# WeatherStation.net
KiCad netlist of a schematic drawn in Altium Designer
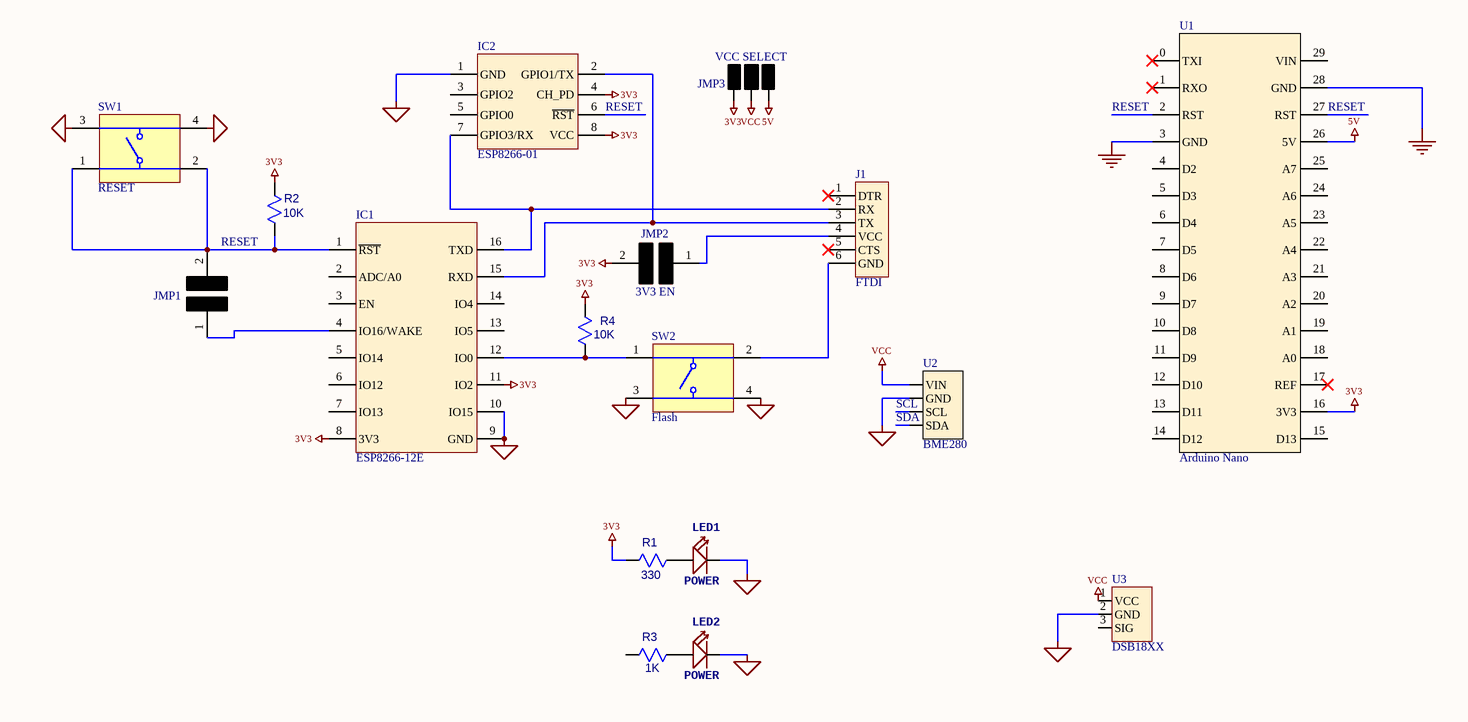
[diagram p0: WeatherStation.SchDoc]

(export (version "E")
  (design (tool "Eeschema 10.0.6"))
  (components
    (comp (ref "IC1")
      (value "ESP8266-12E")
      (footprint "ESP8266-12E")
      (fields (field (name "PART") "ESP8266-12E"))
      (libsource (lib "WeatherStation") (part "ESP8266"))
    )
    (comp (ref "IC2")
      (value "ESP8266-01")
      (footprint "ESP8266-01")
      (libsource (lib "WeatherStation") (part "ESP8266-01"))
    )
    (comp (ref "J1")
      (value "FTDI")
      (footprint "HEAD_1x6")
      (libsource (lib "WeatherStation") (part "FTDI_Connector"))
    )
    (comp (ref "JMP1") (value "JUMP") (footprint "JUMP") (libsource (lib "WeatherStation") (part "JUMP")))
    (comp (ref "JMP2") (value "3V3 EN") (footprint "JUMP") (libsource (lib "WeatherStation") (part "JUMP")))
    (comp (ref "JMP3")
      (value "VCC SELECT")
      (footprint "JMP3")
      (libsource (lib "WeatherStation") (part "JUMP_3"))
    )
    (comp (ref "LED1")
      (value "POWER")
      (footprint "LED-0805")
      (fields (field (name "MPN") "17-215UYC/S530-A3/TR8"))
      (libsource (lib "105848_revD3") (part "SMD-LED-CLEAR-YELLOW(0805)"))
    )
    (comp (ref "LED2")
      (value "POWER")
      (footprint "LED-0805")
      (fields (field (name "MPN") "17-215UYC/S530-A3/TR8"))
      (libsource (lib "105848_revD3") (part "SMD-LED-CLEAR-YELLOW(0805)"))
    )
    (comp (ref "R1")
      (value "330")
      (footprint "CAPC0805(2012)75_N")
      (description "RES_0805")
      (libsource (lib "AltiumIntegratedLibrary") (part "RES_0805"))
    )
    (comp (ref "R2")
      (value "10K")
      (footprint "CAPC0805(2012)75_N")
      (description "RES_0805")
      (libsource (lib "AltiumIntegratedLibrary") (part "RES_0805"))
    )
    (comp (ref "R3")
      (value "1K")
      (footprint "CAPC0805(2012)75_N")
      (description "RES_0805")
      (libsource (lib "AltiumIntegratedLibrary") (part "RES_0805"))
    )
    (comp (ref "R4")
      (value "10K")
      (footprint "CAPC0805(2012)75_N")
      (description "RES_0805")
      (libsource (lib "AltiumIntegratedLibrary") (part "RES_0805"))
    )
    (comp (ref "SW1")
      (value "RESET")
      (footprint "Tactile Switch")
      (libsource (lib "WeatherStation") (part "Tact Switch"))
    )
    (comp (ref "SW2")
      (value "Flash")
      (footprint "Tactile Switch")
      (libsource (lib "") (part "Tact Switch_1"))
    )
    (comp (ref "U1")
      (value "Arduino Nano")
      (footprint "Arduino Nano")
      (libsource (lib "WeatherStation") (part "Arduino Nano"))
    )
    (comp (ref "U2") (value "BME280") (footprint "BME280") (libsource (lib "WeatherStation") (part "BME280")))
    (comp (ref "U3")
      (value "DSB18XX")
      (footprint "HEAD_1x3")
      (libsource (lib "WeatherStation") (part "DALLAS_TEMP"))
    )
  )
  (nets
    (net (code "1") (name "/RESET") (class "Default")
      (node (ref "IC1") (pin "1") (pinfunction "~{RST}_1") (pintype "power_in"))
      (node (ref "IC2") (pin "6") (pinfunction "~{RST}_6") (pintype "power_in"))
      (node (ref "JMP1") (pin "2") (pintype "power_in"))
      (node (ref "R2") (pin "2") (pintype "passive"))
      (node (ref "SW1") (pin "1") (pinfunction "1_1") (pintype "passive"))
      (node (ref "SW1") (pin "2") (pinfunction "2_2") (pintype "passive"))
      (node (ref "U1") (pin "2") (pinfunction "RST_2") (pintype "power_in"))
      (node (ref "U1") (pin "27") (pinfunction "RST_27") (pintype "power_in"))
    )
    (net (code "2") (name "/SCL") (class "Default")
      (node (ref "U2") (pin "3") (pinfunction "SCL_3") (pintype "power_in"))
    )
    (net (code "3") (name "/SDA") (class "Default")
      (node (ref "U2") (pin "4") (pinfunction "SDA_4") (pintype "power_in"))
    )
    (net (code "4") (name "3V3") (class "Default")
      (node (ref "IC1") (pin "11") (pinfunction "IO2_11") (pintype "power_in"))
      (node (ref "IC1") (pin "8") (pinfunction "3V3_8") (pintype "power_in"))
      (node (ref "IC2") (pin "4") (pinfunction "CH_PD_4") (pintype "power_in"))
      (node (ref "IC2") (pin "8") (pinfunction "VCC_8") (pintype "power_in"))
      (node (ref "JMP2") (pin "2") (pintype "power_in"))
      (node (ref "JMP3") (pin "3") (pintype "power_in"))
      (node (ref "R1") (pin "2") (pintype "passive"))
      (node (ref "R2") (pin "1") (pintype "passive"))
      (node (ref "R4") (pin "1") (pintype "passive"))
      (node (ref "U1") (pin "16") (pinfunction "3V3_16") (pintype "power_in"))
    )
    (net (code "5") (name "5V") (class "Default")
      (node (ref "JMP3") (pin "2") (pintype "power_in"))
      (node (ref "U1") (pin "26") (pinfunction "5V_26") (pintype "power_in"))
    )
    (net (code "6") (name "GND") (class "Default")
      (node (ref "IC1") (pin "10") (pinfunction "IO15_10") (pintype "power_in"))
      (node (ref "IC1") (pin "9") (pinfunction "GND_9") (pintype "power_in"))
      (node (ref "IC2") (pin "1") (pinfunction "GND_1") (pintype "power_in"))
      (node (ref "LED1") (pin "-") (pinfunction "-_-") (pintype "passive"))
      (node (ref "LED2") (pin "-") (pinfunction "-_-") (pintype "passive"))
      (node (ref "SW1") (pin "3") (pinfunction "3_3") (pintype "passive"))
      (node (ref "SW1") (pin "4") (pinfunction "4_4") (pintype "passive"))
      (node (ref "SW2") (pin "3") (pinfunction "3_3") (pintype "passive"))
      (node (ref "SW2") (pin "4") (pinfunction "4_4") (pintype "passive"))
      (node (ref "U1") (pin "28") (pinfunction "GND_28") (pintype "power_in"))
      (node (ref "U1") (pin "3") (pinfunction "GND_3") (pintype "power_in"))
      (node (ref "U2") (pin "2") (pinfunction "GND_2") (pintype "power_in"))
      (node (ref "U3") (pin "2") (pinfunction "GND_2") (pintype "power_in"))
    )
    (net (code "7") (name "Net-(IC1-IO0)") (class "Default")
      (node (ref "IC1") (pin "12") (pinfunction "IO0_12") (pintype "power_in"))
      (node (ref "R4") (pin "2") (pintype "passive"))
      (node (ref "SW2") (pin "1") (pinfunction "1_1") (pintype "passive"))
    )
    (net (code "8") (name "Net-(IC1-IO16{slash}WAKE)") (class "Default")
      (node (ref "IC1") (pin "4") (pinfunction "IO16/WAKE_4") (pintype "power_in"))
      (node (ref "JMP1") (pin "1") (pintype "power_in"))
    )
    (net (code "9") (name "Net-(IC1-RXD)") (class "Default")
      (node (ref "IC1") (pin "15") (pinfunction "RXD_15") (pintype "power_in"))
      (node (ref "IC2") (pin "2") (pinfunction "GPIO1/TX_2") (pintype "power_in"))
      (node (ref "J1") (pin "3") (pinfunction "TX_3") (pintype "power_in"))
    )
    (net (code "10") (name "Net-(IC1-TXD)") (class "Default")
      (node (ref "IC1") (pin "16") (pinfunction "TXD_16") (pintype "power_in"))
      (node (ref "IC2") (pin "7") (pinfunction "GPIO3/RX_7") (pintype "power_in"))
      (node (ref "J1") (pin "2") (pinfunction "RX_2") (pintype "power_in"))
    )
    (net (code "11") (name "Net-(J1-GND)") (class "Default")
      (node (ref "J1") (pin "6") (pinfunction "GND_6") (pintype "power_in"))
      (node (ref "SW2") (pin "2") (pinfunction "2_2") (pintype "passive"))
    )
    (net (code "12") (name "Net-(J1-VCC)") (class "Default")
      (node (ref "J1") (pin "4") (pinfunction "VCC_4") (pintype "power_in"))
      (node (ref "JMP2") (pin "1") (pintype "power_in"))
    )
    (net (code "13") (name "Net-(LED1-Pad+)") (class "Default")
      (node (ref "LED1") (pin "+") (pinfunction "+_+") (pintype "passive"))
      (node (ref "R1") (pin "1") (pintype "passive"))
    )
    (net (code "14") (name "Net-(LED2-Pad+)") (class "Default")
      (node (ref "LED2") (pin "+") (pinfunction "+_+") (pintype "passive"))
      (node (ref "R3") (pin "1") (pintype "passive"))
    )
    (net (code "15") (name "VCC") (class "Default")
      (node (ref "JMP3") (pin "1") (pintype "power_in"))
      (node (ref "U2") (pin "1") (pinfunction "VIN_1") (pintype "power_in"))
      (node (ref "U3") (pin "1") (pinfunction "VCC_1") (pintype "power_in"))
    )
    (net (code "16") (name "unconnected-(IC1-ADC{slash}A0-Pad2)") (class "Default")
      (node (ref "IC1") (pin "2") (pinfunction "ADC/A0_2") (pintype "power_in"))
    )
    (net (code "17") (name "unconnected-(IC1-EN-Pad3)") (class "Default")
      (node (ref "IC1") (pin "3") (pinfunction "EN_3") (pintype "power_in"))
    )
    (net (code "18") (name "unconnected-(IC1-IO4-Pad14)") (class "Default")
      (node (ref "IC1") (pin "14") (pinfunction "IO4_14") (pintype "power_in"))
    )
    (net (code "19") (name "unconnected-(IC1-IO5-Pad13)") (class "Default")
      (node (ref "IC1") (pin "13") (pinfunction "IO5_13") (pintype "power_in"))
    )
    (net (code "20") (name "unconnected-(IC1-IO12-Pad6)") (class "Default")
      (node (ref "IC1") (pin "6") (pinfunction "IO12_6") (pintype "power_in"))
    )
    (net (code "21") (name "unconnected-(IC1-IO13-Pad7)") (class "Default")
      (node (ref "IC1") (pin "7") (pinfunction "IO13_7") (pintype "power_in"))
    )
    (net (code "22") (name "unconnected-(IC1-IO14-Pad5)") (class "Default")
      (node (ref "IC1") (pin "5") (pinfunction "IO14_5") (pintype "power_in"))
    )
    (net (code "23") (name "unconnected-(IC2-GPIO0-Pad5)") (class "Default")
      (node (ref "IC2") (pin "5") (pinfunction "GPIO0_5") (pintype "power_in"))
    )
    (net (code "24") (name "unconnected-(IC2-GPIO2-Pad3)") (class "Default")
      (node (ref "IC2") (pin "3") (pinfunction "GPIO2_3") (pintype "power_in"))
    )
    (net (code "25") (name "unconnected-(J1-CTS-Pad5)") (class "Default")
      (node (ref "J1") (pin "5") (pinfunction "CTS_5") (pintype "power_in+no_connect"))
    )
    (net (code "26") (name "unconnected-(J1-DTR-Pad1)") (class "Default")
      (node (ref "J1") (pin "1") (pinfunction "DTR_1") (pintype "power_in+no_connect"))
    )
    (net (code "27") (name "unconnected-(R3-Pad2)") (class "Default")
      (node (ref "R3") (pin "2") (pintype "passive"))
    )
    (net (code "28") (name "unconnected-(U1-A0-Pad18)") (class "Default")
      (node (ref "U1") (pin "18") (pinfunction "A0_18") (pintype "power_in"))
    )
    (net (code "29") (name "unconnected-(U1-A1-Pad19)") (class "Default")
      (node (ref "U1") (pin "19") (pinfunction "A1_19") (pintype "power_in"))
    )
    (net (code "30") (name "unconnected-(U1-A2-Pad20)") (class "Default")
      (node (ref "U1") (pin "20") (pinfunction "A2_20") (pintype "power_in"))
    )
    (net (code "31") (name "unconnected-(U1-A3-Pad21)") (class "Default")
      (node (ref "U1") (pin "21") (pinfunction "A3_21") (pintype "power_in"))
    )
    (net (code "32") (name "unconnected-(U1-A4-Pad22)") (class "Default")
      (node (ref "U1") (pin "22") (pinfunction "A4_22") (pintype "power_in"))
    )
    (net (code "33") (name "unconnected-(U1-A5-Pad23)") (class "Default")
      (node (ref "U1") (pin "23") (pinfunction "A5_23") (pintype "power_in"))
    )
    (net (code "34") (name "unconnected-(U1-A6-Pad24)") (class "Default")
      (node (ref "U1") (pin "24") (pinfunction "A6_24") (pintype "power_in"))
    )
    (net (code "35") (name "unconnected-(U1-A7-Pad25)") (class "Default")
      (node (ref "U1") (pin "25") (pinfunction "A7_25") (pintype "power_in"))
    )
    (net (code "36") (name "unconnected-(U1-D2-Pad4)") (class "Default")
      (node (ref "U1") (pin "4") (pinfunction "D2_4") (pintype "power_in"))
    )
    (net (code "37") (name "unconnected-(U1-D3-Pad5)") (class "Default")
      (node (ref "U1") (pin "5") (pinfunction "D3_5") (pintype "power_in"))
    )
    (net (code "38") (name "unconnected-(U1-D4-Pad6)") (class "Default")
      (node (ref "U1") (pin "6") (pinfunction "D4_6") (pintype "power_in"))
    )
    (net (code "39") (name "unconnected-(U1-D5-Pad7)") (class "Default")
      (node (ref "U1") (pin "7") (pinfunction "D5_7") (pintype "power_in"))
    )
    (net (code "40") (name "unconnected-(U1-D6-Pad8)") (class "Default")
      (node (ref "U1") (pin "8") (pinfunction "D6_8") (pintype "power_in"))
    )
    (net (code "41") (name "unconnected-(U1-D7-Pad9)") (class "Default")
      (node (ref "U1") (pin "9") (pinfunction "D7_9") (pintype "power_in"))
    )
    (net (code "42") (name "unconnected-(U1-D8-Pad10)") (class "Default")
      (node (ref "U1") (pin "10") (pinfunction "D8_10") (pintype "power_in"))
    )
    (net (code "43") (name "unconnected-(U1-D9-Pad11)") (class "Default")
      (node (ref "U1") (pin "11") (pinfunction "D9_11") (pintype "power_in"))
    )
    (net (code "44") (name "unconnected-(U1-D10-Pad12)") (class "Default")
      (node (ref "U1") (pin "12") (pinfunction "D10_12") (pintype "power_in"))
    )
    (net (code "45") (name "unconnected-(U1-D11-Pad13)") (class "Default")
      (node (ref "U1") (pin "13") (pinfunction "D11_13") (pintype "power_in"))
    )
    (net (code "46") (name "unconnected-(U1-D12-Pad14)") (class "Default")
      (node (ref "U1") (pin "14") (pinfunction "D12_14") (pintype "power_in"))
    )
    (net (code "47") (name "unconnected-(U1-D13-Pad15)") (class "Default")
      (node (ref "U1") (pin "15") (pinfunction "D13_15") (pintype "power_in"))
    )
    (net (code "48") (name "unconnected-(U1-REF-Pad17)") (class "Default")
      (node (ref "U1") (pin "17") (pinfunction "REF_17") (pintype "power_in+no_connect"))
    )
    (net (code "49") (name "unconnected-(U1-RXO-Pad1)") (class "Default")
      (node (ref "U1") (pin "1") (pinfunction "RXO_1") (pintype "power_in+no_connect"))
    )
    (net (code "50") (name "unconnected-(U1-TXI-Pad0)") (class "Default")
      (node (ref "U1") (pin "0") (pinfunction "TXI_0") (pintype "power_in+no_connect"))
    )
    (net (code "51") (name "unconnected-(U1-VIN-Pad29)") (class "Default")
      (node (ref "U1") (pin "29") (pinfunction "VIN_29") (pintype "power_in"))
    )
    (net (code "52") (name "unconnected-(U3-SIG-Pad3)") (class "Default")
      (node (ref "U3") (pin "3") (pinfunction "SIG_3") (pintype "power_in"))
    )
  )
)
